# Crystal_Filter.net
KiCad netlist of a schematic drawn in EAGLE
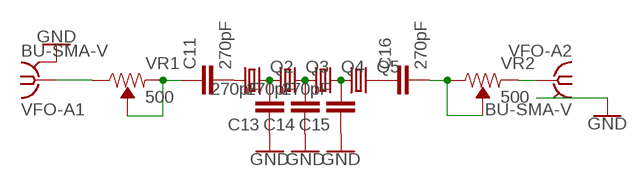
[diagram p0: schematic, sheet 1]

(export (version "E")
  (design (tool "Eeschema 10.0.6"))
  (components
    (comp (ref "C11")
      (value "270pF")
      (footprint "eagle-import:C5B3.5")
      (libsource (lib "eagle-import") (part "C5/3.5"))
    )
    (comp (ref "C13")
      (value "270pF")
      (footprint "eagle-import:C5B3.5")
      (libsource (lib "eagle-import") (part "C5/3.5"))
    )
    (comp (ref "C14")
      (value "270pF")
      (footprint "eagle-import:C5B3.5")
      (libsource (lib "eagle-import") (part "C5/3.5"))
    )
    (comp (ref "C15")
      (value "270pF")
      (footprint "eagle-import:C5B3.5")
      (libsource (lib "eagle-import") (part "C5/3.5"))
    )
    (comp (ref "C16")
      (value "270pF")
      (footprint "eagle-import:C5B3.5")
      (libsource (lib "eagle-import") (part "C5/3.5"))
    )
    (comp (ref "Q2")
      (value "CRYTALHC49S")
      (footprint "eagle-import:HC49_S")
      (libsource (lib "eagle-import") (part "CRYTALHC49S"))
    )
    (comp (ref "Q3")
      (value "CRYTALHC49S")
      (footprint "eagle-import:HC49_S")
      (libsource (lib "eagle-import") (part "CRYTALHC49S"))
    )
    (comp (ref "Q4")
      (value "CRYTALHC49S")
      (footprint "eagle-import:HC49_S")
      (libsource (lib "eagle-import") (part "CRYTALHC49S"))
    )
    (comp (ref "Q5")
      (value "CRYTALHC49S")
      (footprint "eagle-import:HC49_S")
      (libsource (lib "eagle-import") (part "CRYTALHC49S"))
    )
    (comp (ref "VFO-A1")
      (value "BU-SMA-V")
      (footprint "eagle-import:BU-SMA-V")
      (libsource (lib "eagle-import") (part "BU-SMA-V"))
    )
    (comp (ref "VFO-A2")
      (value "BU-SMA-V")
      (footprint "eagle-import:BU-SMA-V")
      (libsource (lib "eagle-import") (part "BU-SMA-V"))
    )
    (comp (ref "VR1")
      (value "500")
      (footprint "eagle-import:TRIMPOT-PTH-3386U")
      (libsource (lib "eagle-import") (part "TRIMPOT-PTH-10MM-KNOB-1/2W-10%"))
    )
    (comp (ref "VR2")
      (value "500")
      (footprint "eagle-import:TRIMPOT-PTH-3386U")
      (libsource (lib "eagle-import") (part "TRIMPOT-PTH-10MM-KNOB-1/2W-10%"))
    )
  )
  (nets
    (net (code "1") (name "GND") (class "Default")
      (node (ref "C13") (pin "1") (pinfunction "1_1") (pintype "passive"))
      (node (ref "C14") (pin "1") (pinfunction "1_1") (pintype "passive"))
      (node (ref "C15") (pin "1") (pinfunction "1_1") (pintype "passive"))
      (node (ref "VFO-A1") (pin "2") (pinfunction "2_2") (pintype "passive"))
      (node (ref "VFO-A1") (pin "3") (pinfunction "2_3") (pintype "passive"))
      (node (ref "VFO-A1") (pin "4") (pinfunction "2_4") (pintype "passive"))
      (node (ref "VFO-A1") (pin "5") (pinfunction "2_5") (pintype "passive"))
      (node (ref "VFO-A2") (pin "2") (pinfunction "2_2") (pintype "passive"))
      (node (ref "VFO-A2") (pin "3") (pinfunction "2_3") (pintype "passive"))
      (node (ref "VFO-A2") (pin "4") (pinfunction "2_4") (pintype "passive"))
      (node (ref "VFO-A2") (pin "5") (pinfunction "2_5") (pintype "passive"))
    )
    (net (code "2") (name "Net-(C11-Pad2)") (class "Default")
      (node (ref "C11") (pin "2") (pinfunction "2_2") (pintype "passive"))
      (node (ref "Q2") (pin "1") (pinfunction "1_1") (pintype "passive"))
    )
    (net (code "3") (name "Net-(C13-Pad2)") (class "Default")
      (node (ref "C13") (pin "2") (pinfunction "2_2") (pintype "passive"))
      (node (ref "Q2") (pin "2") (pinfunction "2_2") (pintype "passive"))
      (node (ref "Q3") (pin "1") (pinfunction "1_1") (pintype "passive"))
    )
    (net (code "4") (name "Net-(C14-Pad2)") (class "Default")
      (node (ref "C14") (pin "2") (pinfunction "2_2") (pintype "passive"))
      (node (ref "Q3") (pin "2") (pinfunction "2_2") (pintype "passive"))
      (node (ref "Q4") (pin "1") (pinfunction "1_1") (pintype "passive"))
    )
    (net (code "5") (name "Net-(C15-Pad2)") (class "Default")
      (node (ref "C15") (pin "2") (pinfunction "2_2") (pintype "passive"))
      (node (ref "Q4") (pin "2") (pinfunction "2_2") (pintype "passive"))
      (node (ref "Q5") (pin "1") (pinfunction "1_1") (pintype "passive"))
    )
    (net (code "6") (name "Net-(C16-Pad1)") (class "Default")
      (node (ref "C16") (pin "1") (pinfunction "1_1") (pintype "passive"))
      (node (ref "Q5") (pin "2") (pinfunction "2_2") (pintype "passive"))
    )
    (net (code "7") (name "Net-(VR1-CCW)") (class "Default")
      (node (ref "C11") (pin "1") (pinfunction "1_1") (pintype "passive"))
      (node (ref "VR1") (pin "1") (pinfunction "CCW_1") (pintype "passive"))
      (node (ref "VR1") (pin "2") (pinfunction "WIPER_2") (pintype "passive"))
    )
    (net (code "8") (name "Net-(VR1-CW)") (class "Default")
      (node (ref "VFO-A1") (pin "1") (pinfunction "1_1") (pintype "passive"))
      (node (ref "VR1") (pin "3") (pinfunction "CW_3") (pintype "passive"))
    )
    (net (code "9") (name "Net-(VR2-CCW)") (class "Default")
      (node (ref "VFO-A2") (pin "1") (pinfunction "1_1") (pintype "passive"))
      (node (ref "VR2") (pin "1") (pinfunction "CCW_1") (pintype "passive"))
    )
    (net (code "10") (name "Net-(VR2-CW)") (class "Default")
      (node (ref "C16") (pin "2") (pinfunction "2_2") (pintype "passive"))
      (node (ref "VR2") (pin "2") (pinfunction "WIPER_2") (pintype "passive"))
      (node (ref "VR2") (pin "3") (pinfunction "CW_3") (pintype "passive"))
    )
  )
)
